# AFE.net
KiCad netlist of a schematic drawn in Altium Designer
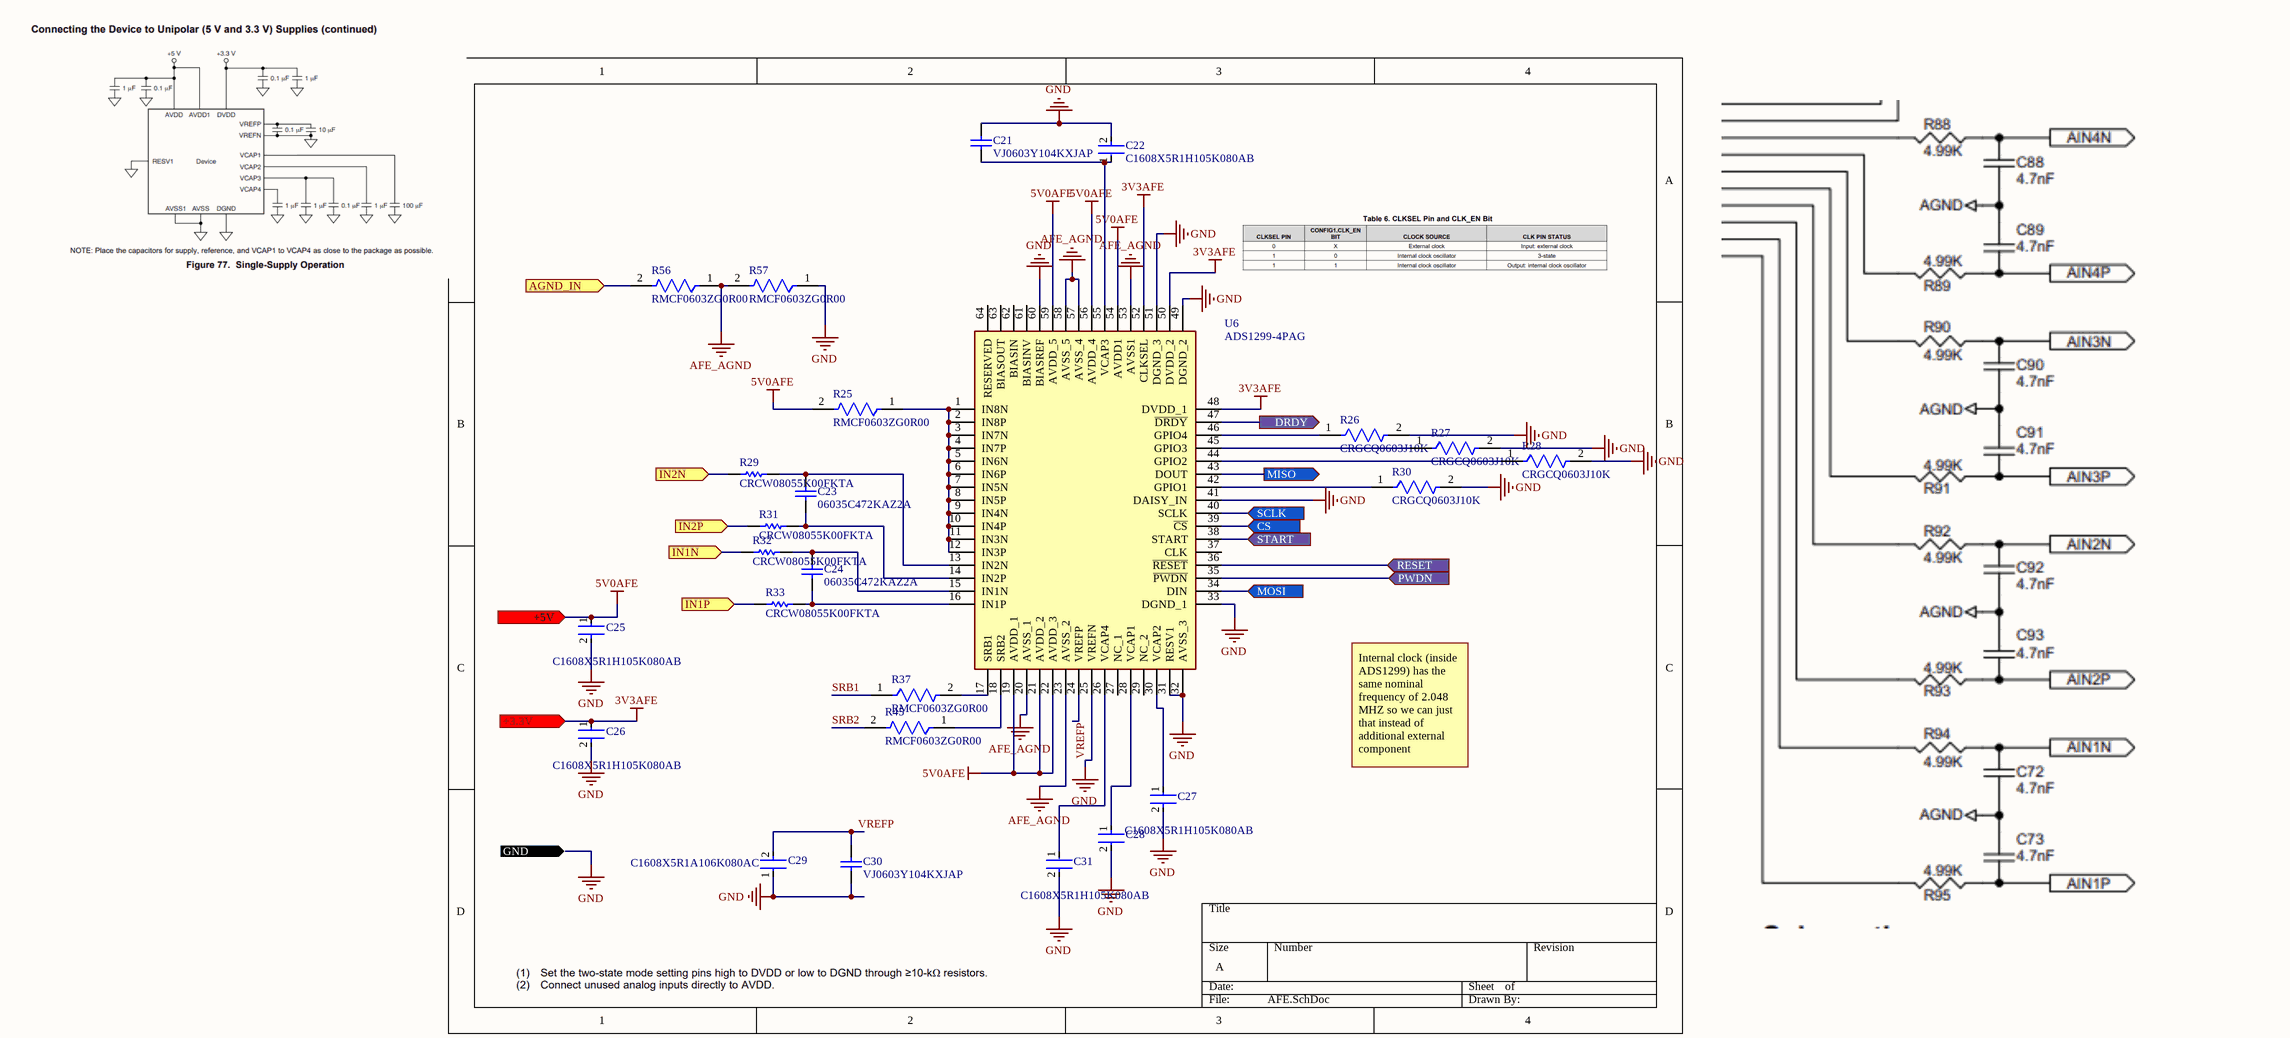
[diagram p0: AFE.SchDoc]

(export (version "E")
  (design (tool "Eeschema 10.0.6"))
  (components
    (comp (ref "C21")
      (value "VJ0603Y104KXJAP")
      (footprint "CAPC1608X92X38NL15T08")
      (fields (field (name "MANUFACTURER") "Vitramon"))
      (libsource (lib "Altium Content Vault") (part "CAP"))
    )
    (comp (ref "C22")
      (value "C1608X5R1H105K080AB")
      (footprint "FP-C1608-080-0_1-IPC_B")
      (description "Multilayer Ceramic Capacitors 1μF ±10% 50V X5R SMD 0603")
      (fields (field (name "VOLTAGE") "50V") (field (name "TOLERANCE") "10%"))
      (libsource (lib "Altium Content Vault") (part "236180d848d6139a670b325ea6854c9"))
    )
    (comp (ref "C23")
      (value "06035C472KAZ2A")
      (footprint "CAPC1608X90X35LL15T15")
      (fields (field (name "MANUFACTURER") "AVX Interconnect / Elco"))
      (libsource (lib "Altium Content Vault") (part "CAP"))
    )
    (comp (ref "C24")
      (value "06035C472KAZ2A")
      (footprint "CAPC1608X90X35LL15T15")
      (fields (field (name "MANUFACTURER") "AVX Interconnect / Elco"))
      (libsource (lib "Altium Content Vault") (part "CAP"))
    )
    (comp (ref "C25")
      (value "C1608X5R1H105K080AB")
      (footprint "FP-C1608-080-0_1-IPC_B")
      (description "Multilayer Ceramic Capacitors 1μF ±10% 50V X5R SMD 0603")
      (fields (field (name "VOLTAGE") "50V") (field (name "TOLERANCE") "10%"))
      (libsource (lib "Altium Content Vault") (part "236180d848d6139a670b325ea6854c9"))
    )
    (comp (ref "C26")
      (value "C1608X5R1H105K080AB")
      (footprint "FP-C1608-080-0_1-IPC_B")
      (description "Multilayer Ceramic Capacitors 1μF ±10% 50V X5R SMD 0603")
      (fields (field (name "VOLTAGE") "50V") (field (name "TOLERANCE") "10%"))
      (libsource (lib "Altium Content Vault") (part "236180d848d6139a670b325ea6854c9"))
    )
    (comp (ref "C27")
      (value "C1608X5R1H105K080AB")
      (footprint "FP-C1608-080-0_1-IPC_B")
      (description "Multilayer Ceramic Capacitors 1μF ±10% 50V X5R SMD 0603")
      (fields (field (name "VOLTAGE") "50V") (field (name "TOLERANCE") "10%"))
      (libsource (lib "Altium Content Vault") (part "236180d848d6139a670b325ea6854c9"))
    )
    (comp (ref "C28")
      (value "GRM21BR60J107ME15K")
      (footprint "FP-GRM21B-0_2-e0_2_0_7-IPC_B")
      (description "Chip Multilayer Ceramic Capacitors for General Purpose, 0805, 100uF, X5R, 15%, 20%, 6.3V")
      (fields (field (name "TOLERANCE") "20%"))
      (libsource (lib "Altium Content Vault") (part "b4654b650e69147ec39a6b967a45e02"))
    )
    (comp (ref "C29")
      (value "C1608X5R1A106K080AC")
      (footprint "FP-C1608-080-0_1-MFG")
      (description "Multilayer Ceramic Capacitors 10μF ±10% 10V X5R SMD 0603")
      (fields (field (name "VOLTAGE") "10V") (field (name "TOLERANCE") "10%"))
      (libsource (lib "Altium Content Vault") (part "236180d848d6139a670b325ea6854c9"))
    )
    (comp (ref "C30")
      (value "VJ0603Y104KXJAP")
      (footprint "CAPC1608X92X38NL15T08")
      (fields (field (name "MANUFACTURER") "Vitramon"))
      (libsource (lib "Altium Content Vault") (part "CAP"))
    )
    (comp (ref "C31")
      (value "C1608X5R1H105K080AB")
      (footprint "FP-C1608-080-0_1-IPC_B")
      (description "Multilayer Ceramic Capacitors 1μF ±10% 50V X5R SMD 0603")
      (fields (field (name "VOLTAGE") "50V") (field (name "TOLERANCE") "10%"))
      (libsource (lib "Altium Content Vault") (part "236180d848d6139a670b325ea6854c9"))
    )
    (comp (ref "R25")
      (value "RMCF0603ZG0R00")
      (footprint "FP-RMCF0603-IPC_B")
      (description "0Ω ±0 0.1W 0603 Thick Film Chip Resistor AEC-Q200 compliant")
      (libsource (lib "Altium Content Vault") (part "1029c3af85768c4190bb7ad29bc67b5"))
    )
    (comp (ref "R26")
      (value "CRGCQ0603J10K")
      (footprint "FP-CRGCQ0603-IPC_C")
      (description "CRGCQ 0603 10K 5%")
      (fields
        (field (name "TOLERANCE") "0.05")
        (field (name "OCTOPART") "https://octopart.com/crgcq0603j10k-te+connectivity-91018097")
      )
      (libsource (lib "Altium Content Vault") (part "1029c3af85768c4190bb7ad29bc67b5"))
    )
    (comp (ref "R27")
      (value "CRGCQ0603J10K")
      (footprint "FP-CRGCQ0603-IPC_C")
      (description "CRGCQ 0603 10K 5%")
      (fields
        (field (name "TOLERANCE") "0.05")
        (field (name "OCTOPART") "https://octopart.com/crgcq0603j10k-te+connectivity-91018097")
      )
      (libsource (lib "Altium Content Vault") (part "1029c3af85768c4190bb7ad29bc67b5"))
    )
    (comp (ref "R28")
      (value "CRGCQ0603J10K")
      (footprint "FP-CRGCQ0603-IPC_C")
      (description "CRGCQ 0603 10K 5%")
      (fields
        (field (name "TOLERANCE") "0.05")
        (field (name "OCTOPART") "https://octopart.com/crgcq0603j10k-te+connectivity-91018097")
      )
      (libsource (lib "Altium Content Vault") (part "1029c3af85768c4190bb7ad29bc67b5"))
    )
    (comp (ref "R29")
      (value "CRCW08055K00FKTA")
      (footprint "RESC2013X50X30ML20T20")
      (fields (field (name "MANUFACTURER") "Vishay Dale"))
      (libsource (lib "Altium Content Vault") (part "RES"))
    )
    (comp (ref "R30")
      (value "CRGCQ0603J10K")
      (footprint "FP-CRGCQ0603-IPC_C")
      (description "CRGCQ 0603 10K 5%")
      (fields
        (field (name "TOLERANCE") "0.05")
        (field (name "OCTOPART") "https://octopart.com/crgcq0603j10k-te+connectivity-91018097")
      )
      (libsource (lib "Altium Content Vault") (part "1029c3af85768c4190bb7ad29bc67b5"))
    )
    (comp (ref "R31")
      (value "CRCW08055K00FKTA")
      (footprint "RESC2013X50X30ML20T20")
      (fields (field (name "MANUFACTURER") "Vishay Dale"))
      (libsource (lib "Altium Content Vault") (part "RES"))
    )
    (comp (ref "R32")
      (value "CRCW08055K00FKTA")
      (footprint "RESC2013X50X30ML20T20")
      (fields (field (name "MANUFACTURER") "Vishay Dale"))
      (libsource (lib "Altium Content Vault") (part "RES"))
    )
    (comp (ref "R33")
      (value "CRCW08055K00FKTA")
      (footprint "RESC2013X50X30ML20T20")
      (fields (field (name "MANUFACTURER") "Vishay Dale"))
      (libsource (lib "Altium Content Vault") (part "RES"))
    )
    (comp (ref "R37")
      (value "RMCF0603ZG0R00")
      (footprint "FP-RMCF0603-IPC_B")
      (description "0Ω ±0 0.1W 0603 Thick Film Chip Resistor AEC-Q200 compliant")
      (libsource (lib "Altium Content Vault") (part "1029c3af85768c4190bb7ad29bc67b5"))
    )
    (comp (ref "R45")
      (value "RMCF0603ZG0R00")
      (footprint "FP-RMCF0603-IPC_B")
      (description "0Ω ±0 0.1W 0603 Thick Film Chip Resistor AEC-Q200 compliant")
      (libsource (lib "Altium Content Vault") (part "1029c3af85768c4190bb7ad29bc67b5"))
    )
    (comp (ref "R56")
      (value "RMCF0603ZG0R00")
      (footprint "FP-RMCF0603-IPC_B")
      (description "0Ω ±0 0.1W 0603 Thick Film Chip Resistor AEC-Q200 compliant")
      (libsource (lib "Altium Content Vault") (part "1029c3af85768c4190bb7ad29bc67b5"))
    )
    (comp (ref "R57")
      (value "RMCF0603ZG0R00")
      (footprint "FP-RMCF0603-IPC_B")
      (description "0Ω ±0 0.1W 0603 Thick Film Chip Resistor AEC-Q200 compliant")
      (libsource (lib "Altium Content Vault") (part "1029c3af85768c4190bb7ad29bc67b5"))
    )
    (comp (ref "U6")
      (value "ADS1299-4PAG")
      (footprint "QFP50P1200X1200X120-64N")
      (description "Low-Noise, 4-Channel, 24-Bit Analog-to-Digital Converter for Biopotential Measurements")
      (fields (field (name "MOUSER PART NUMBER") "595-ADS1299-4PAG"))
      (libsource (lib "ADS1299-4PAG") (part "ADS1299-4PAG"))
    )
  )
  (nets
    (net (code "1") (name "/AGND_IN") (class "Default")
      (node (ref "R56") (pin "2") (pinfunction "2_2") (pintype "passive"))
    )
    (net (code "2") (name "/CS") (class "Default")
      (node (ref "U6") (pin "39") (pinfunction "~{CS}_39") (pintype "passive"))
    )
    (net (code "3") (name "/DRDY") (class "Default")
      (node (ref "U6") (pin "47") (pinfunction "~{DRDY}_47") (pintype "passive"))
    )
    (net (code "4") (name "/IN1N") (class "Default")
      (node (ref "R32") (pin "1") (pinfunction "1_1") (pintype "passive"))
    )
    (net (code "5") (name "/IN1P") (class "Default")
      (node (ref "R33") (pin "1") (pinfunction "1_1") (pintype "passive"))
    )
    (net (code "6") (name "/IN2N") (class "Default")
      (node (ref "R29") (pin "1") (pinfunction "1_1") (pintype "passive"))
    )
    (net (code "7") (name "/IN2P") (class "Default")
      (node (ref "R31") (pin "1") (pinfunction "1_1") (pintype "passive"))
    )
    (net (code "8") (name "/MISO") (class "Default")
      (node (ref "U6") (pin "43") (pinfunction "DOUT_43") (pintype "passive"))
    )
    (net (code "9") (name "/MOSI") (class "Default")
      (node (ref "U6") (pin "34") (pinfunction "DIN_34") (pintype "passive"))
    )
    (net (code "10") (name "/PWDN") (class "Default")
      (node (ref "U6") (pin "35") (pinfunction "~{PWDN}_35") (pintype "passive"))
    )
    (net (code "11") (name "/RESET") (class "Default")
      (node (ref "U6") (pin "36") (pinfunction "~{RESET}_36") (pintype "passive"))
    )
    (net (code "12") (name "/SCLK") (class "Default")
      (node (ref "U6") (pin "40") (pinfunction "SCLK_40") (pintype "passive"))
    )
    (net (code "13") (name "/SRB1") (class "Default")
      (node (ref "R37") (pin "1") (pinfunction "1_1") (pintype "passive"))
    )
    (net (code "14") (name "/SRB2") (class "Default")
      (node (ref "R45") (pin "2") (pinfunction "2_2") (pintype "passive"))
    )
    (net (code "15") (name "/START") (class "Default")
      (node (ref "U6") (pin "38") (pinfunction "START_38") (pintype "passive"))
    )
    (net (code "16") (name "/VREFP") (class "Default")
      (node (ref "C29") (pin "2") (pinfunction "2_2") (pintype "passive"))
      (node (ref "C30") (pin "2") (pinfunction "2_2") (pintype "passive"))
      (node (ref "U6") (pin "24") (pinfunction "VREFP_24") (pintype "passive"))
    )
    (net (code "17") (name "3V3AFE") (class "Default")
      (node (ref "C26") (pin "1") (pinfunction "1_1") (pintype "passive"))
      (node (ref "U6") (pin "48") (pinfunction "DVDD_1_48") (pintype "passive"))
      (node (ref "U6") (pin "50") (pinfunction "DVDD_2_50") (pintype "passive"))
      (node (ref "U6") (pin "52") (pinfunction "CLKSEL_52") (pintype "passive"))
    )
    (net (code "18") (name "5V0AFE") (class "Default")
      (node (ref "C25") (pin "1") (pinfunction "1_1") (pintype "passive"))
      (node (ref "R25") (pin "2") (pinfunction "2_2") (pintype "passive"))
      (node (ref "U6") (pin "19") (pinfunction "AVDD_1_19") (pintype "passive"))
      (node (ref "U6") (pin "21") (pinfunction "AVDD_2_21") (pintype "passive"))
      (node (ref "U6") (pin "22") (pinfunction "AVDD_3_22") (pintype "passive"))
      (node (ref "U6") (pin "54") (pinfunction "AVDD1_54") (pintype "passive"))
      (node (ref "U6") (pin "56") (pinfunction "AVDD_4_56") (pintype "passive"))
      (node (ref "U6") (pin "59") (pinfunction "AVDD_5_59") (pintype "passive"))
    )
    (net (code "19") (name "AFE_AGND") (class "Default")
      (node (ref "R56") (pin "1") (pinfunction "1_1") (pintype "passive"))
      (node (ref "R57") (pin "2") (pinfunction "2_2") (pintype "passive"))
      (node (ref "U6") (pin "20") (pinfunction "AVSS_1_20") (pintype "passive"))
      (node (ref "U6") (pin "23") (pinfunction "AVSS_2_23") (pintype "passive"))
      (node (ref "U6") (pin "53") (pinfunction "AVSS1_53") (pintype "passive"))
      (node (ref "U6") (pin "57") (pinfunction "AVSS_4_57") (pintype "passive"))
      (node (ref "U6") (pin "58") (pinfunction "AVSS_5_58") (pintype "passive"))
    )
    (net (code "20") (name "GND") (class "Default")
      (node (ref "C21") (pin "2") (pinfunction "2_2") (pintype "passive"))
      (node (ref "C22") (pin "2") (pinfunction "2_2") (pintype "passive"))
      (node (ref "C25") (pin "2") (pinfunction "2_2") (pintype "passive"))
      (node (ref "C26") (pin "2") (pinfunction "2_2") (pintype "passive"))
      (node (ref "C27") (pin "2") (pinfunction "2_2") (pintype "passive"))
      (node (ref "C28") (pin "2") (pinfunction "2_2") (pintype "passive"))
      (node (ref "C29") (pin "1") (pinfunction "1_1") (pintype "passive"))
      (node (ref "C30") (pin "1") (pinfunction "1_1") (pintype "passive"))
      (node (ref "C31") (pin "2") (pinfunction "2_2") (pintype "passive"))
      (node (ref "R26") (pin "2") (pinfunction "2_2") (pintype "passive"))
      (node (ref "R27") (pin "2") (pinfunction "2_2") (pintype "passive"))
      (node (ref "R28") (pin "2") (pinfunction "2_2") (pintype "passive"))
      (node (ref "R30") (pin "2") (pinfunction "2_2") (pintype "passive"))
      (node (ref "R57") (pin "1") (pinfunction "1_1") (pintype "passive"))
      (node (ref "U6") (pin "25") (pinfunction "VREFN_25") (pintype "passive"))
      (node (ref "U6") (pin "31") (pinfunction "RESV1_31") (pintype "passive"))
      (node (ref "U6") (pin "32") (pinfunction "AVSS_3_32") (pintype "passive"))
      (node (ref "U6") (pin "33") (pinfunction "DGND_1_33") (pintype "passive"))
      (node (ref "U6") (pin "41") (pinfunction "DAISY_IN_41") (pintype "passive"))
      (node (ref "U6") (pin "49") (pinfunction "DGND_2_49") (pintype "passive"))
      (node (ref "U6") (pin "51") (pinfunction "DGND_3_51") (pintype "passive"))
      (node (ref "U6") (pin "60") (pinfunction "BIASREF_60") (pintype "passive"))
    )
    (net (code "21") (name "Net-(U6-GPIO1)") (class "Default")
      (node (ref "R30") (pin "1") (pinfunction "1_1") (pintype "passive"))
      (node (ref "U6") (pin "42") (pinfunction "GPIO1_42") (pintype "passive"))
    )
    (net (code "22") (name "Net-(U6-GPIO2)") (class "Default")
      (node (ref "R28") (pin "1") (pinfunction "1_1") (pintype "passive"))
      (node (ref "U6") (pin "44") (pinfunction "GPIO2_44") (pintype "passive"))
    )
    (net (code "23") (name "Net-(U6-GPIO3)") (class "Default")
      (node (ref "R27") (pin "1") (pinfunction "1_1") (pintype "passive"))
      (node (ref "U6") (pin "45") (pinfunction "GPIO3_45") (pintype "passive"))
    )
    (net (code "24") (name "Net-(U6-GPIO4)") (class "Default")
      (node (ref "R26") (pin "1") (pinfunction "1_1") (pintype "passive"))
      (node (ref "U6") (pin "46") (pinfunction "GPIO4_46") (pintype "passive"))
    )
    (net (code "25") (name "Net-(U6-IN1N)") (class "Default")
      (node (ref "C24") (pin "1") (pinfunction "1_1") (pintype "passive"))
      (node (ref "R32") (pin "2") (pinfunction "2_2") (pintype "passive"))
      (node (ref "U6") (pin "15") (pinfunction "IN1N_15") (pintype "passive"))
    )
    (net (code "26") (name "Net-(U6-IN1P)") (class "Default")
      (node (ref "C24") (pin "2") (pinfunction "2_2") (pintype "passive"))
      (node (ref "R33") (pin "2") (pinfunction "2_2") (pintype "passive"))
      (node (ref "U6") (pin "16") (pinfunction "IN1P_16") (pintype "passive"))
    )
    (net (code "27") (name "Net-(U6-IN2N)") (class "Default")
      (node (ref "C23") (pin "1") (pinfunction "1_1") (pintype "passive"))
      (node (ref "R29") (pin "2") (pinfunction "2_2") (pintype "passive"))
      (node (ref "U6") (pin "13") (pinfunction "IN2N_13") (pintype "passive"))
    )
    (net (code "28") (name "Net-(U6-IN2P)") (class "Default")
      (node (ref "C23") (pin "2") (pinfunction "2_2") (pintype "passive"))
      (node (ref "R31") (pin "2") (pinfunction "2_2") (pintype "passive"))
      (node (ref "U6") (pin "14") (pinfunction "IN2P_14") (pintype "passive"))
    )
    (net (code "29") (name "Net-(U6-IN3N)") (class "Default")
      (node (ref "R25") (pin "1") (pinfunction "1_1") (pintype "passive"))
      (node (ref "U6") (pin "1") (pinfunction "IN8N_1") (pintype "passive"))
      (node (ref "U6") (pin "10") (pinfunction "IN4P_10") (pintype "passive"))
      (node (ref "U6") (pin "11") (pinfunction "IN3N_11") (pintype "passive"))
      (node (ref "U6") (pin "12") (pinfunction "IN3P_12") (pintype "passive"))
      (node (ref "U6") (pin "2") (pinfunction "IN8P_2") (pintype "passive"))
      (node (ref "U6") (pin "3") (pinfunction "IN7N_3") (pintype "passive"))
      (node (ref "U6") (pin "4") (pinfunction "IN7P_4") (pintype "passive"))
      (node (ref "U6") (pin "5") (pinfunction "IN6N_5") (pintype "passive"))
      (node (ref "U6") (pin "6") (pinfunction "IN6P_6") (pintype "passive"))
      (node (ref "U6") (pin "7") (pinfunction "IN5N_7") (pintype "passive"))
      (node (ref "U6") (pin "8") (pinfunction "IN5P_8") (pintype "passive"))
      (node (ref "U6") (pin "9") (pinfunction "IN4N_9") (pintype "passive"))
    )
    (net (code "30") (name "Net-(U6-SRB1)") (class "Default")
      (node (ref "R37") (pin "2") (pinfunction "2_2") (pintype "passive"))
      (node (ref "U6") (pin "17") (pinfunction "SRB1_17") (pintype "passive"))
    )
    (net (code "31") (name "Net-(U6-SRB2)") (class "Default")
      (node (ref "R45") (pin "1") (pinfunction "1_1") (pintype "passive"))
      (node (ref "U6") (pin "18") (pinfunction "SRB2_18") (pintype "passive"))
    )
    (net (code "32") (name "Net-(U6-VCAP1)") (class "Default")
      (node (ref "C28") (pin "1") (pinfunction "1_1") (pintype "passive"))
      (node (ref "U6") (pin "28") (pinfunction "VCAP1_28") (pintype "passive"))
    )
    (net (code "33") (name "Net-(U6-VCAP2)") (class "Default")
      (node (ref "C27") (pin "1") (pinfunction "1_1") (pintype "passive"))
      (node (ref "U6") (pin "30") (pinfunction "VCAP2_30") (pintype "passive"))
    )
    (net (code "34") (name "Net-(U6-VCAP3)") (class "Default")
      (node (ref "C21") (pin "1") (pinfunction "1_1") (pintype "passive"))
      (node (ref "C22") (pin "1") (pinfunction "1_1") (pintype "passive"))
      (node (ref "U6") (pin "55") (pinfunction "VCAP3_55") (pintype "passive"))
    )
    (net (code "35") (name "Net-(U6-VCAP4)") (class "Default")
      (node (ref "C31") (pin "1") (pinfunction "1_1") (pintype "passive"))
      (node (ref "U6") (pin "26") (pinfunction "VCAP4_26") (pintype "passive"))
    )
    (net (code "36") (name "unconnected-(U6-BIASIN-Pad62)") (class "Default")
      (node (ref "U6") (pin "62") (pinfunction "BIASIN_62") (pintype "passive"))
    )
    (net (code "37") (name "unconnected-(U6-BIASINV-Pad61)") (class "Default")
      (node (ref "U6") (pin "61") (pinfunction "BIASINV_61") (pintype "passive"))
    )
    (net (code "38") (name "unconnected-(U6-BIASOUT-Pad63)") (class "Default")
      (node (ref "U6") (pin "63") (pinfunction "BIASOUT_63") (pintype "passive"))
    )
    (net (code "39") (name "unconnected-(U6-CLK-Pad37)") (class "Default")
      (node (ref "U6") (pin "37") (pinfunction "CLK_37") (pintype "passive"))
    )
    (net (code "40") (name "unconnected-(U6-NC_1-Pad27)") (class "Default")
      (node (ref "U6") (pin "27") (pinfunction "NC_1_27") (pintype "passive"))
    )
    (net (code "41") (name "unconnected-(U6-NC_2-Pad29)") (class "Default")
      (node (ref "U6") (pin "29") (pinfunction "NC_2_29") (pintype "passive"))
    )
    (net (code "42") (name "unconnected-(U6-RESERVED-Pad64)") (class "Default")
      (node (ref "U6") (pin "64") (pinfunction "RESERVED_64") (pintype "passive"))
    )
  )
)
